# 02-TxCoil.net
KiCad netlist of a schematic drawn in Altium Designer
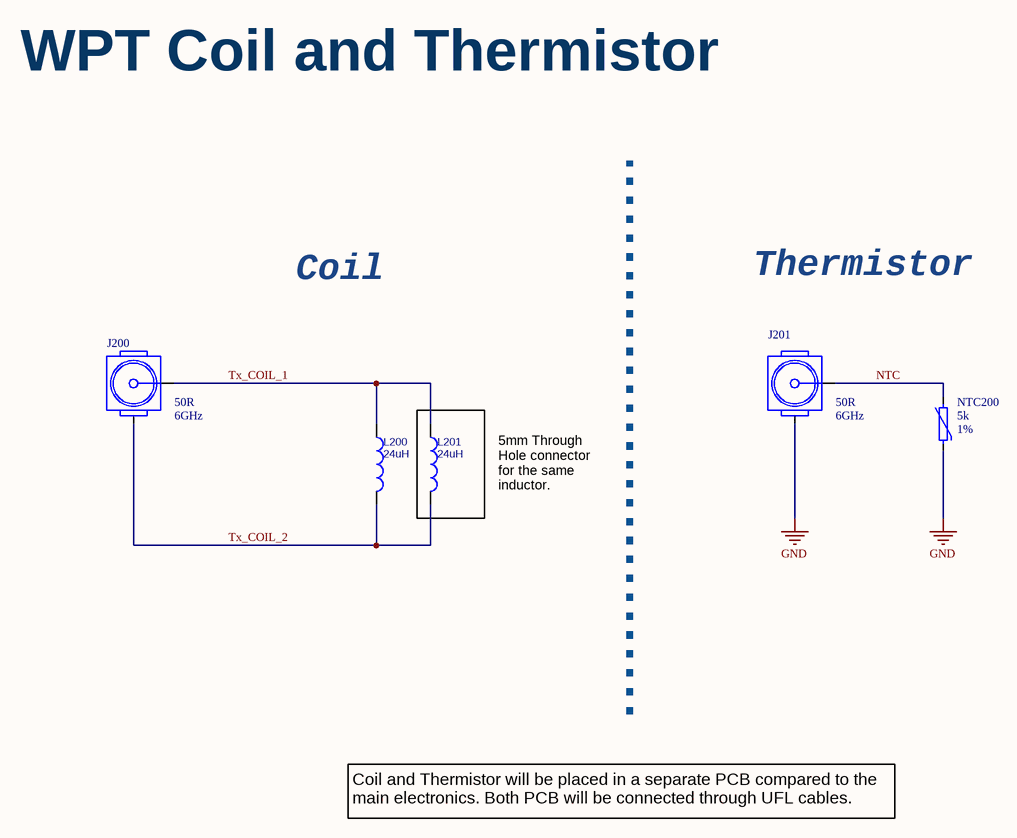
[diagram p0: 02-TxCoil.SchDoc]

(export (version "E")
  (design (tool "Eeschema 10.0.6"))
  (components
    (comp (ref "J200")
      (value "U.FL-R-SMT-1(10)")
      (footprint "FP-U_FL-R-SMT-1_10-MFG")
      (description "RF Connector, 1 Contact(s), Male, Board Mount, Surface Mount Terminal, Receptacle")
      (fields
        (field (name "MANUFACTURER") "Hirose")
        (field (name "CHARACTERISTIC IMPEDANCE") "50R")
        (field (name "OPERATING FREQUENCY-MAX") "6GHz")
      )
      (libsource (lib "MP-LIBRARY") (part "U.FL-R-SMT-1(10)"))
    )
    (comp (ref "J201")
      (value "U.FL-R-SMT-1(10)")
      (footprint "FP-U_FL-R-SMT-1_10-MFG")
      (description "RF Connector, 1 Contact(s), Male, Board Mount, Surface Mount Terminal, Receptacle")
      (fields
        (field (name "MANUFACTURER") "Hirose")
        (field (name "CHARACTERISTIC IMPEDANCE") "50R")
        (field (name "OPERATING FREQUENCY-MAX") "6GHz")
      )
      (libsource (lib "MP-LIBRARY") (part "U.FL-R-SMT-1(10)"))
    )
    (comp (ref "L200")
      (value "24uH")
      (footprint "760308100110 SMD")
      (description "1 Coil, 2 Layer 24µH Wireless Charging Coil Transmitter 70mOhm")
      (fields (field (name "MANUFACTURER PART NUMBER") "760308100110") (field (name "MANUFACTURER") "Wurth"))
      (libsource (lib "MP-LIBRARY") (part "760308100110"))
    )
    (comp (ref "L201")
      (value "24uH")
      (footprint "Coil_pads-5mm-ThroughHole")
      (description "1 Coil, 2 Layer 24µH Wireless Charging Coil Transmitter 70mOhm")
      (fields (field (name "MANUFACTURER PART NUMBER") "760308100110") (field (name "MANUFACTURER") "Wurth"))
      (libsource (lib "MP-LIBRARY") (part "760308100110"))
    )
    (comp (ref "NTC200")
      (value "5k")
      (footprint "NTC0603")
      (description "NTC SMD 0603, 5KOHM, 1%, B25/85")
      (fields
        (field (name "MANUFACTURER") "Vishay Dale")
        (field (name "MANUFACTURER PART NUMBER") "NTCS0603E3502FLT")
        (field (name "TOLERANCE") "1%")
      )
      (libsource (lib "MP-LIBRARY") (part "NTCS0603E3502FLT"))
    )
  )
  (nets
    (net (code "1") (name "/NTC") (class "Default")
      (node (ref "J201") (pin "1") (pinfunction "1_1") (pintype "passive"))
      (node (ref "NTC200") (pin "2") (pinfunction "2_2") (pintype "passive"))
    )
    (net (code "2") (name "/Tx_COIL_1") (class "Default")
      (node (ref "J200") (pin "1") (pinfunction "1_1") (pintype "passive"))
      (node (ref "L200") (pin "2") (pinfunction "2_2") (pintype "passive"))
      (node (ref "L201") (pin "2") (pinfunction "2_2") (pintype "passive"))
    )
    (net (code "3") (name "/Tx_COIL_2") (class "Default")
      (node (ref "J200") (pin "2") (pinfunction "2_2") (pintype "passive"))
      (node (ref "L200") (pin "1") (pinfunction "1_1") (pintype "passive"))
      (node (ref "L201") (pin "1") (pinfunction "1_1") (pintype "passive"))
    )
    (net (code "4") (name "GND") (class "Default")
      (node (ref "J201") (pin "2") (pinfunction "2_2") (pintype "passive"))
      (node (ref "NTC200") (pin "1") (pinfunction "1_1") (pintype "passive"))
    )
  )
)
